# Sheet1.net
KiCad netlist of a schematic drawn in Altium Designer
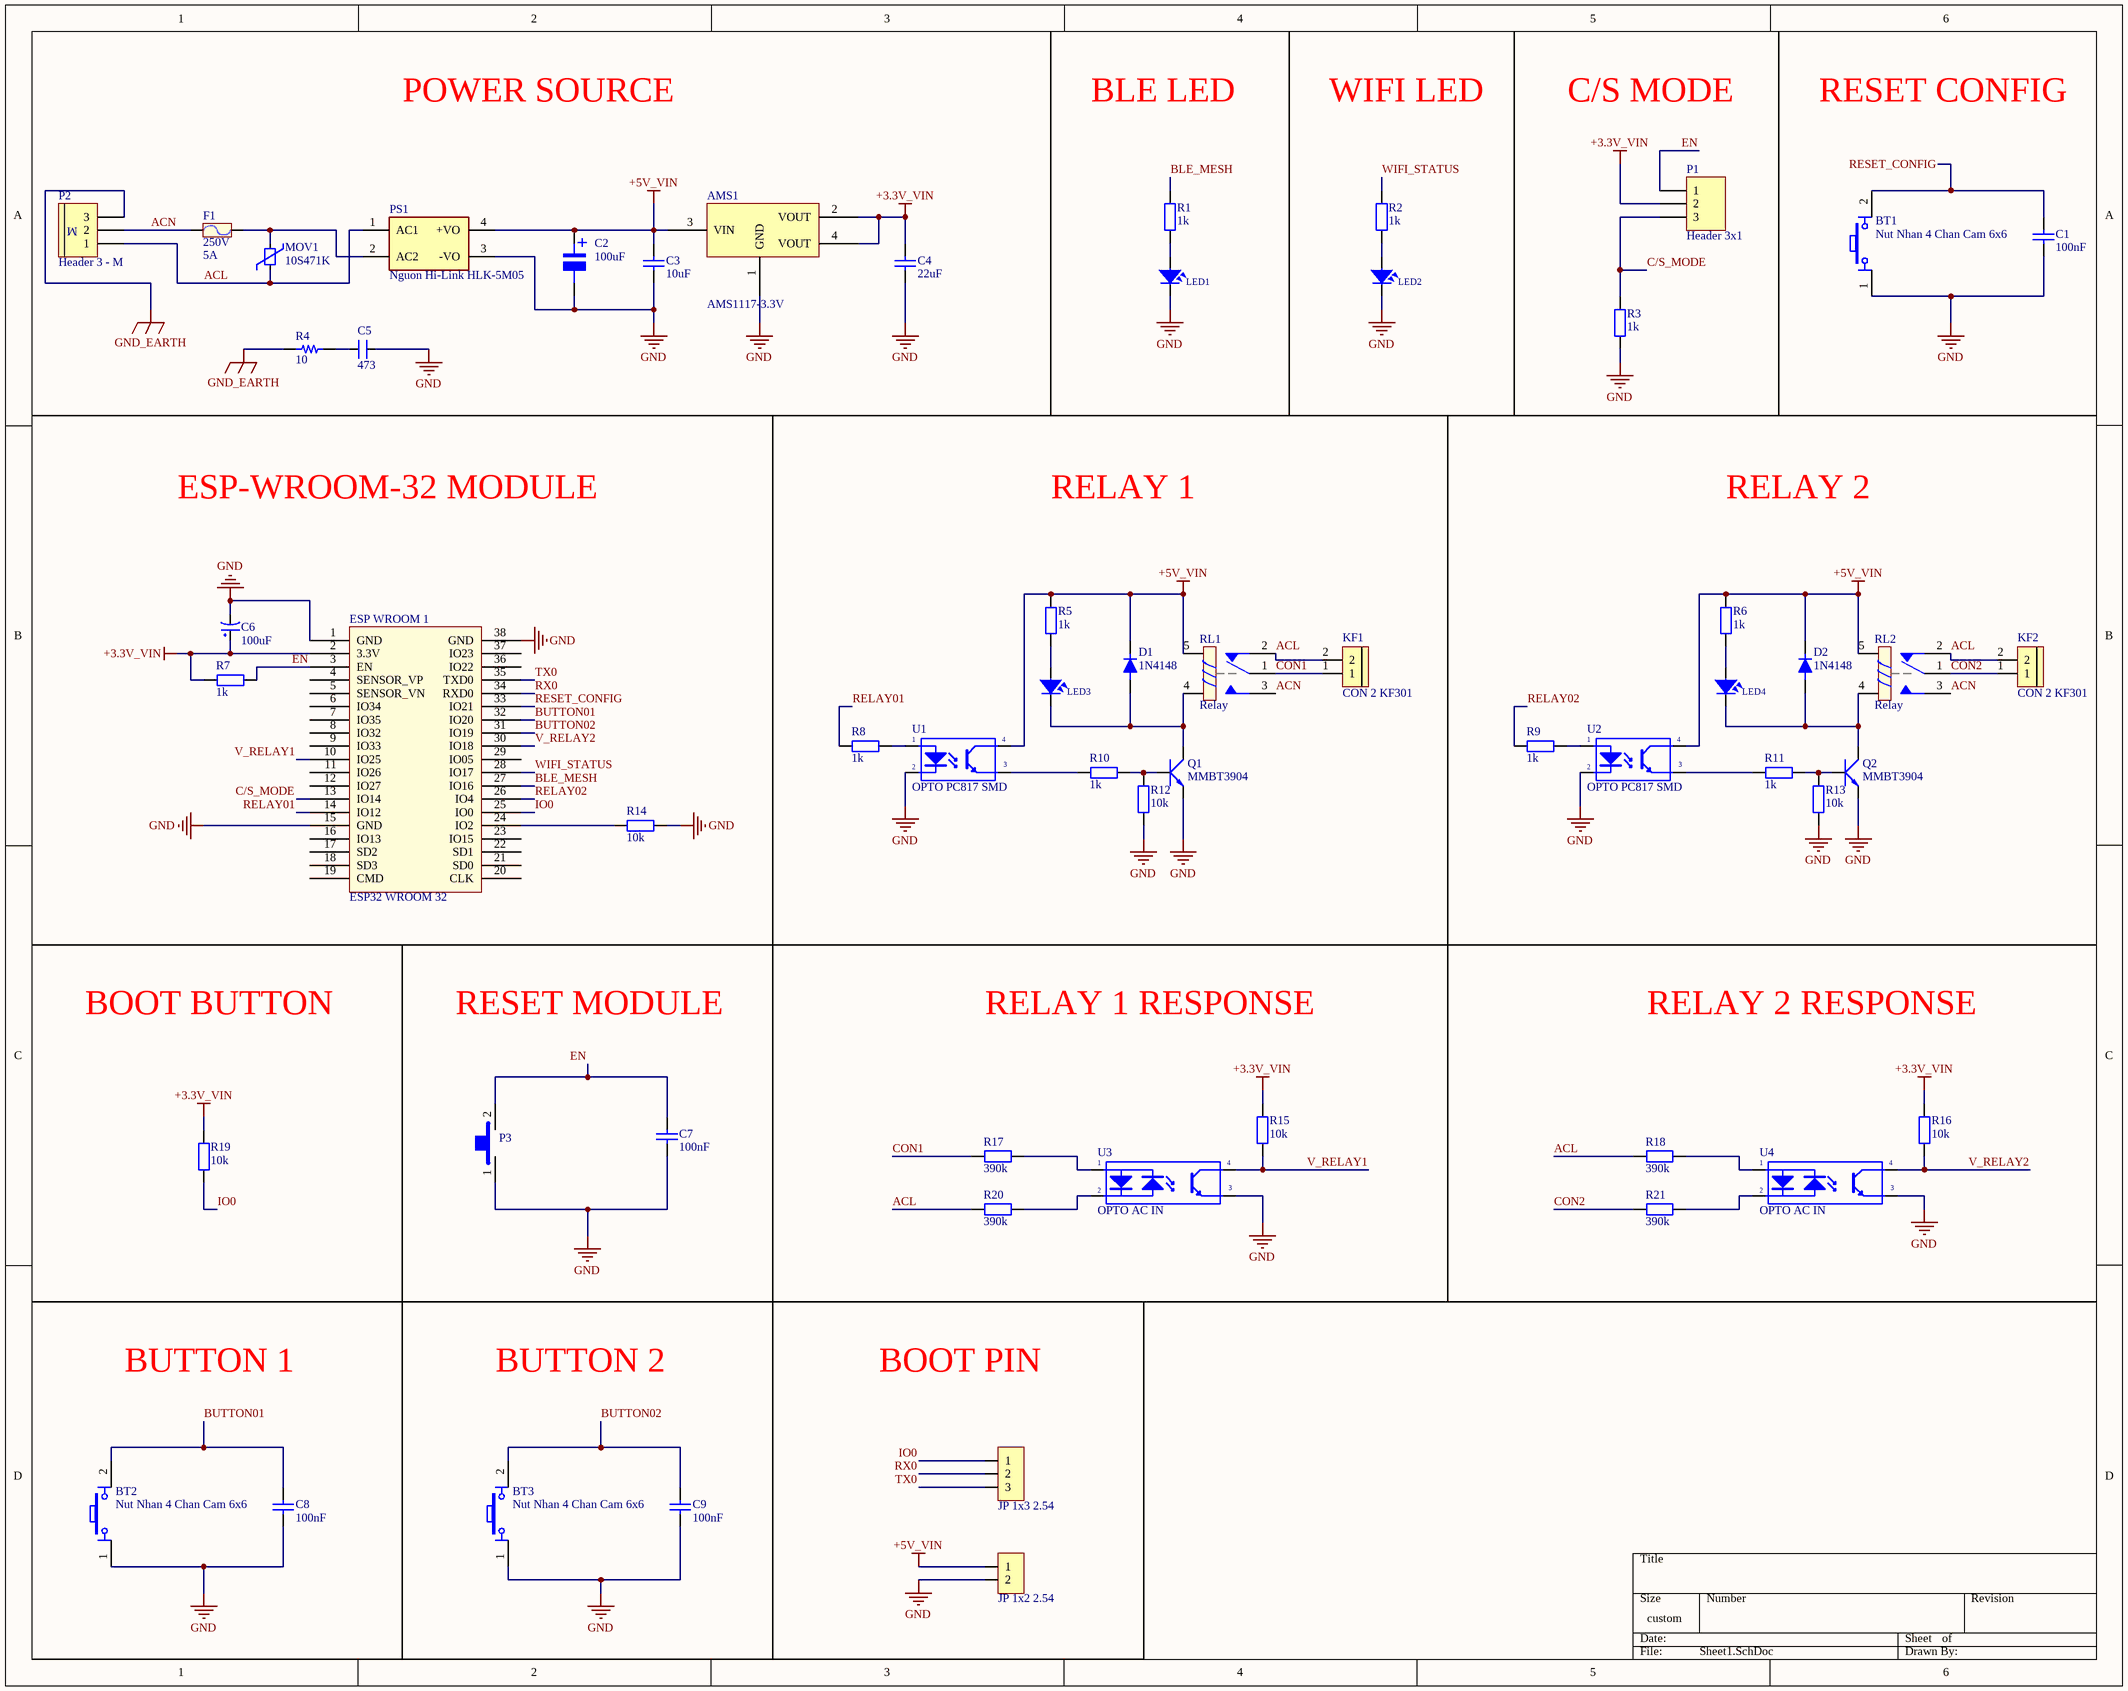
[diagram p0: Sheet1.SchDoc]

(export (version "E")
  (design (tool "Eeschema 10.0.6"))
  (components
    (comp (ref "AMS1")
      (value "AMS1117-3.3V")
      (footprint "SOT223")
      (description "Dán")
      (libsource (lib "Altium_Lib_by_KhueNguyenCreator") (part "AMS1117 SMD"))
    )
    (comp (ref "BT1")
      (value "Nut Nhan 4 Chan Cam 6x6")
      (footprint "Nut Nhan 4 Chan Cam 6x6")
      (description "Nut Nhan 4 Chan 6x6mm")
      (libsource (lib "Altium_Lib_by_KhueNguyenCreator") (part "Nut Nhan 4 Chan Cam 6x6"))
    )
    (comp (ref "BT2")
      (value "Nut Nhan 4 Chan Cam 6x6")
      (footprint "Nut Nhan 4 Chan Cam 6x6")
      (description "Nut Nhan 4 Chan 6x6mm")
      (libsource (lib "Altium_Lib_by_KhueNguyenCreator") (part "Nut Nhan 4 Chan Cam 6x6"))
    )
    (comp (ref "BT3")
      (value "Nut Nhan 4 Chan Cam 6x6")
      (footprint "Nut Nhan 4 Chan Cam 6x6")
      (description "Nut Nhan 4 Chan 6x6mm")
      (libsource (lib "Altium_Lib_by_KhueNguyenCreator") (part "Nut Nhan 4 Chan Cam 6x6"))
    )
    (comp (ref "C1")
      (value "100nF")
      (footprint "C0603C/1608MM")
      (description "Cap Ceramic 0.1uF 16V X7R 5% SMD 0603 125C T/R")
      (fields
        (field (name "MANUFACTURER") "Yageo")
        (field (name "MANUFACTURER PART NUMBER") "CC0603JRX7R7BB104")
      )
      (libsource (lib "Howard") (part "CAP CER 100nF 16V 5% X7R 0603"))
    )
    (comp (ref "C2")
      (value "100uF")
      (footprint "tu nhom 6.3 (d)")
      (description "Dán")
      (libsource (lib "Altium_Lib_by_KhueNguyenCreator") (part "Tu Nhom 100uF 16V"))
    )
    (comp (ref "C3")
      (value "10uF")
      (footprint "C0603C/1608MM")
      (description "CAP CER 0603 10uF 16V X7R 10%")
      (libsource (lib "Howard") (part "CAP CER 10uF 16V X7R 0603"))
    )
    (comp (ref "C4")
      (value "22uF")
      (footprint "C0603C/1608MM")
      (description "CAP CER 0603 10uF 16V X7R 10%")
      (libsource (lib "Howard") (part "CAP CER 10uF 16V X7R 0603"))
    )
    (comp (ref "C5")
      (value "473")
      (footprint "CN3")
      (description "Cap np W0.3")
      (fields (field (name "COPYRIGHT") "VanDungEvn"))
      (libsource (lib "syhaunguyen") (part "CN3"))
    )
    (comp (ref "C6")
      (value "100uF")
      (footprint "tu tantalum smd3528")
      (description "Dán")
      (libsource (lib "Altium_Lib_by_KhueNguyenCreator") (part "Tu tantalum 100uF 6.3V SMD3528"))
    )
    (comp (ref "C7")
      (value "100nF")
      (footprint "C0603C/1608MM")
      (description "Cap Ceramic 0.1uF 16V X7R 5% SMD 0603 125C T/R")
      (fields
        (field (name "MANUFACTURER") "Yageo")
        (field (name "MANUFACTURER PART NUMBER") "CC0603JRX7R7BB104")
      )
      (libsource (lib "Howard") (part "CAP CER 100nF 16V 5% X7R 0603"))
    )
    (comp (ref "C8")
      (value "100nF")
      (footprint "C0603C/1608MM")
      (description "Cap Ceramic 0.1uF 16V X7R 5% SMD 0603 125C T/R")
      (fields
        (field (name "MANUFACTURER") "Yageo")
        (field (name "MANUFACTURER PART NUMBER") "CC0603JRX7R7BB104")
      )
      (libsource (lib "Howard") (part "CAP CER 100nF 16V 5% X7R 0603"))
    )
    (comp (ref "C9")
      (value "100nF")
      (footprint "C0603C/1608MM")
      (description "Cap Ceramic 0.1uF 16V X7R 5% SMD 0603 125C T/R")
      (fields
        (field (name "MANUFACTURER") "Yageo")
        (field (name "MANUFACTURER PART NUMBER") "CC0603JRX7R7BB104")
      )
      (libsource (lib "Howard") (part "CAP CER 100nF 16V 5% X7R 0603"))
    )
    (comp (ref "D1")
      (value "1N4148")
      (footprint "SOD-323")
      (description "DIODE GEN PURP 75V 150MA DO35")
      (libsource (lib "Howard") (part "DIODE GEN PURP 75V 150MA DO35"))
    )
    (comp (ref "D2")
      (value "1N4148")
      (footprint "SOD-323")
      (description "DIODE GEN PURP 75V 150MA DO35")
      (libsource (lib "Howard") (part "DIODE GEN PURP 75V 150MA DO35"))
    )
    (comp (ref "ESP WROOM 1")
      (value "ESP32 WROOM 32")
      (footprint "ESP32-WROOM-32D")
      (libsource (lib "Altium_Lib_by_KhueNguyenCreator") (part "ESP32 WROOM 32"))
    )
    (comp (ref "F1")
      (value "5A220V")
      (footprint "FUSE_VERTICAL")
      (description "FUSE 220V 5A RADIAL")
      (fields (field (name "VOLTAGE - RATED") "250V") (field (name "CURRENT RATING (AMPS)") "5A"))
      (libsource (lib "Howard") (part "Fuse"))
    )
    (comp (ref "JP1")
      (value "JP 1x3 2.54")
      (footprint "JP 1x3 DT")
      (description "Cắm")
      (libsource (lib "Altium_Lib_by_KhueNguyenCreator") (part "JP 1x3 2.54 Duc Thang"))
    )
    (comp (ref "JP2")
      (value "JP 1x2 2.54")
      (footprint "JP 1x2 DT")
      (description "Cắm")
      (libsource (lib "Altium_Lib_by_KhueNguyenCreator") (part "JP 1x2 2.54 Duc Thang"))
    )
    (comp (ref "KF1")
      (value "CON 2 KF301")
      (footprint "Con 2 KF301 5.08")
      (description "Cắm")
      (libsource (lib "Altium_Lib_by_KhueNguyenCreator") (part "CON 2 KF301"))
    )
    (comp (ref "KF2")
      (value "CON 2 KF301")
      (footprint "Con 2 KF301 5.08")
      (description "Cắm")
      (libsource (lib "Altium_Lib_by_KhueNguyenCreator") (part "CON 2 KF301"))
    )
    (comp (ref "LED1")
      (value "LED SMD")
      (footprint "SM-LED-0805-Blue")
      (libsource (lib "My library altium") (part "LED SMD 0805"))
    )
    (comp (ref "LED2")
      (value "LED SMD")
      (footprint "SM-LED-0805-Blue")
      (libsource (lib "My library altium") (part "LED SMD 0805"))
    )
    (comp (ref "LED3")
      (value "LED SMD")
      (footprint "SM-LED-0805-Blue")
      (libsource (lib "My library altium") (part "LED SMD 0805"))
    )
    (comp (ref "LED4")
      (value "LED SMD")
      (footprint "SM-LED-0805-Blue")
      (libsource (lib "My library altium") (part "LED SMD 0805"))
    )
    (comp (ref "MOV1")
      (value "10S471K")
      (footprint "10S471K")
      (description "VARISTOR 470V 2.5KA DISC 10MM")
      (fields
        (field (name "MANUFACTURER2_PART#") "10D391K 390V 10mm")
        (field (name "MANUFACTURER1_PART#") "MOV-10D391K")
      )
      (libsource (lib "Howard") (part "MOV 10S471K"))
    )
    (comp (ref "P1")
      (value "Header 3x1")
      (footprint "HDR1X3")
      (description "Header, 3-Pin, pitch 2.54mm")
      (libsource (lib "BYTECH_HW_LIB_2019") (part "Header 3x1"))
    )
    (comp (ref "P2")
      (value "Header 3 - M")
      (footprint "Medium - Header 3")
      (description "Header, 3-Pin, Medium")
      (fields (field (name "PUBLISHER") "Altium Limited"))
      (libsource (lib "04.Header-Connecter") (part "Header 3 - M"))
    )
    (comp (ref "P3")
      (value "~")
      (footprint "SW 2P SMD")
      (description "SMD Mini Push Button Switch 2 Pin 3x6x2.7mm")
      (fields (field (name "MPN") "SMD Mini Push Button 2 SMD"))
      (libsource (lib "BYTECH_HW_LIB_2019") (part "Button 2 SMD"))
    )
    (comp (ref "PS1")
      (value "Nguon Hi-Link HLK-5M05")
      (footprint "Nguon HI-LINK 5M05")
      (description "AC DC 220V to 5V 5W 5Watt Isolated Switching Step-Down Power Supply Module Converter")
      (fields (field (name "MF") "Hi-link") (field (name "MP") "HLK-5M05"))
      (libsource (lib "Altium_Lib_by_KhueNguyenCreator") (part "Nguon Hi-Link HLK-5M05"))
    )
    (comp (ref "Q1")
      (value "MMBT3904")
      (footprint "Howard:SOT 23")
      (description "Bipolar (BJT) Transistor NPN 40 V 200 mA 300MHz 350 mW Surface Mount SOT-23")
      (fields (field (name "MANUFACTURER") "MCC") (field (name "MANUFACTURER PART NUMBER") "2SD882-GR-BP"))
      (libsource (lib "Howard") (part "TRANS NPN 40V 0.2A SOT23"))
    )
    (comp (ref "Q2")
      (value "MMBT3904")
      (footprint "Howard:SOT 23")
      (description "Bipolar (BJT) Transistor NPN 40 V 200 mA 300MHz 350 mW Surface Mount SOT-23")
      (fields (field (name "MANUFACTURER") "MCC") (field (name "MANUFACTURER PART NUMBER") "2SD882-GR-BP"))
      (libsource (lib "Howard") (part "TRANS NPN 40V 0.2A SOT23"))
    )
    (comp (ref "R1")
      (value "1k")
      (footprint "tro smd 0603")
      (description "Dán")
      (libsource (lib "Altium_Lib_by_KhueNguyenCreator") (part "Tro 0603 1% 1k"))
    )
    (comp (ref "R2")
      (value "1k")
      (footprint "tro smd 0603")
      (description "Dán")
      (libsource (lib "Altium_Lib_by_KhueNguyenCreator") (part "Tro 0603 1% 1k"))
    )
    (comp (ref "R3")
      (value "1k")
      (footprint "tro smd 0603")
      (description "Dán")
      (libsource (lib "Altium_Lib_by_KhueNguyenCreator") (part "Tro 0603 1% 1k"))
    )
    (comp (ref "R4")
      (value "10")
      (footprint "R1206B/3216MM")
      (description "Surface Mount Thick Film Resistor, RC Series, 3.3Mohm, 100 mW, - 5%, 50 V, 1206")
      (fields
        (field (name "MANUFACTURER") "Yageo")
        (field (name "MANUFACTURER PART NUMBER") "RC1206JR-073M3L")
      )
      (libsource (lib "Howard") (part "RES SMD 3.3M OHM 5% 1/4W 1206"))
    )
    (comp (ref "R5")
      (value "1k")
      (footprint "tro smd 0603")
      (description "Dán")
      (libsource (lib "Altium_Lib_by_KhueNguyenCreator") (part "Tro 0603 1% 1k"))
    )
    (comp (ref "R6")
      (value "1k")
      (footprint "tro smd 0603")
      (description "Dán")
      (libsource (lib "Altium_Lib_by_KhueNguyenCreator") (part "Tro 0603 1% 1k"))
    )
    (comp (ref "R7")
      (value "1k")
      (footprint "tro smd 0603")
      (description "Dán")
      (libsource (lib "Altium_Lib_by_KhueNguyenCreator") (part "Tro 0603 1% 1k"))
    )
    (comp (ref "R8")
      (value "1k")
      (footprint "tro smd 0603")
      (description "Dán")
      (libsource (lib "Altium_Lib_by_KhueNguyenCreator") (part "Tro 0603 1% 1k"))
    )
    (comp (ref "R9")
      (value "1k")
      (footprint "tro smd 0603")
      (description "Dán")
      (libsource (lib "Altium_Lib_by_KhueNguyenCreator") (part "Tro 0603 1% 1k"))
    )
    (comp (ref "R10")
      (value "1k")
      (footprint "tro smd 0603")
      (description "Dán")
      (libsource (lib "Altium_Lib_by_KhueNguyenCreator") (part "Tro 0603 1% 1k"))
    )
    (comp (ref "R11")
      (value "1k")
      (footprint "tro smd 0603")
      (description "Dán")
      (libsource (lib "Altium_Lib_by_KhueNguyenCreator") (part "Tro 0603 1% 1k"))
    )
    (comp (ref "R12")
      (value "10k")
      (footprint "tro smd 0603")
      (description "Dán")
      (libsource (lib "Altium_Lib_by_KhueNguyenCreator") (part "Tro 0603 1% 10k"))
    )
    (comp (ref "R13")
      (value "10k")
      (footprint "tro smd 0603")
      (description "Dán")
      (libsource (lib "Altium_Lib_by_KhueNguyenCreator") (part "Tro 0603 1% 10k"))
    )
    (comp (ref "R14")
      (value "10k")
      (footprint "tro smd 0603")
      (description "Dán")
      (libsource (lib "Altium_Lib_by_KhueNguyenCreator") (part "Tro 0603 1% 10k"))
    )
    (comp (ref "R15")
      (value "10k")
      (footprint "tro smd 0603")
      (description "Dán")
      (libsource (lib "Altium_Lib_by_KhueNguyenCreator") (part "Tro 0603 1% 10k"))
    )
    (comp (ref "R16")
      (value "10k")
      (footprint "tro smd 0603")
      (description "Dán")
      (libsource (lib "Altium_Lib_by_KhueNguyenCreator") (part "Tro 0603 1% 10k"))
    )
    (comp (ref "R17")
      (value "390k")
      (footprint "tro smd 1206")
      (description "Dán")
      (libsource (lib "Altium_Lib_by_KhueNguyenCreator") (part "Tro 1206 1% 390k"))
    )
    (comp (ref "R18")
      (value "390k")
      (footprint "tro smd 1206")
      (description "Dán")
      (libsource (lib "Altium_Lib_by_KhueNguyenCreator") (part "Tro 1206 1% 390k"))
    )
    (comp (ref "R19")
      (value "10k")
      (footprint "tro smd 0603")
      (description "Dán")
      (libsource (lib "Altium_Lib_by_KhueNguyenCreator") (part "Tro 0603 1% 10k"))
    )
    (comp (ref "R20")
      (value "390k")
      (footprint "tro smd 1206")
      (description "Dán")
      (libsource (lib "Altium_Lib_by_KhueNguyenCreator") (part "Tro 1206 1% 390k"))
    )
    (comp (ref "R21")
      (value "390k")
      (footprint "tro smd 1206")
      (description "Dán")
      (libsource (lib "Altium_Lib_by_KhueNguyenCreator") (part "Tro 1206 1% 390k"))
    )
    (comp (ref "RL1")
      (value "Relay")
      (footprint "Relay 5 Chan SRD")
      (description "Relay 5 Chan")
      (libsource (lib "Altium_Lib_by_KhueNguyenCreator") (part "Relay 5 Chan SRD"))
    )
    (comp (ref "RL2")
      (value "Relay")
      (footprint "Relay 5 Chan SRD")
      (description "Relay 5 Chan")
      (libsource (lib "Altium_Lib_by_KhueNguyenCreator") (part "Relay 5 Chan SRD"))
    )
    (comp (ref "U1")
      (value "OPTO PC817 SMD")
      (footprint "SOP4")
      (description "Single Opto")
      (libsource (lib "Altium_Lib_by_KhueNguyenCreator") (part "OPTO PC817 SMD"))
    )
    (comp (ref "U2")
      (value "OPTO PC817 SMD")
      (footprint "SOP4")
      (description "Single Opto")
      (libsource (lib "Altium_Lib_by_KhueNguyenCreator") (part "OPTO PC817 SMD"))
    )
    (comp (ref "U3")
      (value "OPTO AC IN")
      (footprint "LTV-354T")
      (description "AC INPUT Opto")
      (libsource (lib "Schlib1") (part "LTV-354T"))
    )
    (comp (ref "U4")
      (value "OPTO AC IN")
      (footprint "LTV-354T")
      (description "AC INPUT Opto")
      (libsource (lib "Schlib1") (part "LTV-354T"))
    )
  )
  (nets
    (net (code "1") (name "+3.3V_VIN") (class "Default")
      (node (ref "AMS1") (pin "2") (pinfunction "VOUT_2") (pintype "passive"))
      (node (ref "AMS1") (pin "4") (pinfunction "VOUT_4") (pintype "passive"))
      (node (ref "C4") (pin "2") (pinfunction "2_2") (pintype "passive"))
      (node (ref "C6") (pin "1") (pinfunction "1_1") (pintype "passive"))
      (node (ref "ESP WROOM 1") (pin "2") (pinfunction "3.3V_2") (pintype "passive"))
      (node (ref "P1") (pin "2") (pinfunction "2_2") (pintype "passive"))
      (node (ref "R15") (pin "2") (pinfunction "2_2") (pintype "passive"))
      (node (ref "R16") (pin "2") (pinfunction "2_2") (pintype "passive"))
      (node (ref "R19") (pin "1") (pinfunction "1_1") (pintype "passive"))
      (node (ref "R7") (pin "2") (pinfunction "2_2") (pintype "passive"))
    )
    (net (code "2") (name "+5V_VIN") (class "Default")
      (node (ref "AMS1") (pin "3") (pinfunction "VIN_3") (pintype "passive"))
      (node (ref "C2") (pin "1") (pinfunction "1_1") (pintype "passive"))
      (node (ref "C3") (pin "2") (pinfunction "2_2") (pintype "passive"))
      (node (ref "D1") (pin "2") (pinfunction "CATHODE_2") (pintype "passive"))
      (node (ref "D2") (pin "2") (pinfunction "CATHODE_2") (pintype "passive"))
      (node (ref "JP2") (pin "1") (pinfunction "1_1") (pintype "passive"))
      (node (ref "PS1") (pin "4") (pinfunction "+VO_4") (pintype "passive"))
      (node (ref "R5") (pin "2") (pinfunction "2_2") (pintype "passive"))
      (node (ref "R6") (pin "2") (pinfunction "2_2") (pintype "passive"))
      (node (ref "RL1") (pin "5") (pinfunction "5_5") (pintype "passive"))
      (node (ref "RL2") (pin "5") (pinfunction "5_5") (pintype "passive"))
      (node (ref "U1") (pin "4") (pinfunction "C_4") (pintype "passive"))
      (node (ref "U2") (pin "4") (pinfunction "C_4") (pintype "passive"))
    )
    (net (code "3") (name "/ACL") (class "Default")
      (node (ref "KF1") (pin "2") (pinfunction "2_2") (pintype "passive"))
      (node (ref "KF2") (pin "2") (pinfunction "2_2") (pintype "passive"))
      (node (ref "MOV1") (pin "2") (pinfunction "2_2") (pintype "passive"))
      (node (ref "P2") (pin "1") (pinfunction "1_1") (pintype "passive"))
      (node (ref "PS1") (pin "1") (pinfunction "AC1_1") (pintype "passive"))
      (node (ref "R18") (pin "1") (pinfunction "1_1") (pintype "passive"))
      (node (ref "R20") (pin "1") (pinfunction "1_1") (pintype "passive"))
      (node (ref "RL1") (pin "2") (pinfunction "2_2") (pintype "passive"))
      (node (ref "RL2") (pin "2") (pinfunction "2_2") (pintype "passive"))
    )
    (net (code "4") (name "/ACN") (class "Default")
      (node (ref "F1") (pin "2") (pinfunction "2_2") (pintype "passive"))
      (node (ref "P2") (pin "2") (pinfunction "2_2") (pintype "passive"))
      (node (ref "RL1") (pin "3") (pinfunction "3_3") (pintype "passive"))
      (node (ref "RL2") (pin "3") (pinfunction "3_3") (pintype "passive"))
    )
    (net (code "5") (name "/BLE_MESH") (class "Default")
      (node (ref "ESP WROOM 1") (pin "27") (pinfunction "IO16_27") (pintype "passive"))
      (node (ref "R1") (pin "2") (pinfunction "2_2") (pintype "passive"))
    )
    (net (code "6") (name "/BUTTON01") (class "Default")
      (node (ref "BT2") (pin "2") (pintype "passive"))
      (node (ref "C8") (pin "1") (pinfunction "1_1") (pintype "passive"))
      (node (ref "ESP WROOM 1") (pin "32") (pinfunction "IO20_32") (pintype "passive"))
    )
    (net (code "7") (name "/BUTTON02") (class "Default")
      (node (ref "BT3") (pin "2") (pintype "passive"))
      (node (ref "C9") (pin "1") (pinfunction "1_1") (pintype "passive"))
      (node (ref "ESP WROOM 1") (pin "31") (pinfunction "IO19_31") (pintype "passive"))
    )
    (net (code "8") (name "/CON1") (class "Default")
      (node (ref "KF1") (pin "1") (pinfunction "1_1") (pintype "passive"))
      (node (ref "R17") (pin "1") (pinfunction "1_1") (pintype "passive"))
      (node (ref "RL1") (pin "1") (pinfunction "1_1") (pintype "passive"))
    )
    (net (code "9") (name "/CON2") (class "Default")
      (node (ref "KF2") (pin "1") (pinfunction "1_1") (pintype "passive"))
      (node (ref "R21") (pin "1") (pinfunction "1_1") (pintype "passive"))
      (node (ref "RL2") (pin "1") (pinfunction "1_1") (pintype "passive"))
    )
    (net (code "10") (name "/C{slash}S_MODE") (class "Default")
      (node (ref "ESP WROOM 1") (pin "13") (pinfunction "IO14_13") (pintype "passive"))
      (node (ref "P1") (pin "3") (pinfunction "3_3") (pintype "passive"))
      (node (ref "R3") (pin "2") (pinfunction "2_2") (pintype "passive"))
    )
    (net (code "11") (name "/EN") (class "Default")
      (node (ref "C7") (pin "1") (pinfunction "1_1") (pintype "passive"))
      (node (ref "ESP WROOM 1") (pin "3") (pinfunction "EN_3") (pintype "passive"))
      (node (ref "P1") (pin "1") (pinfunction "1_1") (pintype "passive"))
      (node (ref "P3") (pin "2") (pinfunction "2_2") (pintype "passive"))
      (node (ref "R7") (pin "1") (pinfunction "1_1") (pintype "passive"))
    )
    (net (code "12") (name "/IO0") (class "Default")
      (node (ref "ESP WROOM 1") (pin "25") (pinfunction "IO0_25") (pintype "passive"))
      (node (ref "JP1") (pin "1") (pinfunction "1_1") (pintype "passive"))
      (node (ref "R19") (pin "2") (pinfunction "2_2") (pintype "passive"))
    )
    (net (code "13") (name "/RELAY01") (class "Default")
      (node (ref "ESP WROOM 1") (pin "14") (pinfunction "IO12_14") (pintype "passive"))
      (node (ref "R8") (pin "1") (pinfunction "1_1") (pintype "passive"))
    )
    (net (code "14") (name "/RELAY02") (class "Default")
      (node (ref "ESP WROOM 1") (pin "26") (pinfunction "IO4_26") (pintype "passive"))
      (node (ref "R9") (pin "1") (pinfunction "1_1") (pintype "passive"))
    )
    (net (code "15") (name "/RESET_CONFIG") (class "Default")
      (node (ref "BT1") (pin "2") (pintype "passive"))
      (node (ref "C1") (pin "1") (pinfunction "1_1") (pintype "passive"))
      (node (ref "ESP WROOM 1") (pin "33") (pinfunction "IO21_33") (pintype "passive"))
    )
    (net (code "16") (name "/RX0") (class "Default")
      (node (ref "ESP WROOM 1") (pin "34") (pinfunction "RXD0_34") (pintype "passive"))
      (node (ref "JP1") (pin "2") (pinfunction "2_2") (pintype "passive"))
    )
    (net (code "17") (name "/TX0") (class "Default")
      (node (ref "ESP WROOM 1") (pin "35") (pinfunction "TXD0_35") (pintype "passive"))
      (node (ref "JP1") (pin "3") (pinfunction "3_3") (pintype "passive"))
    )
    (net (code "18") (name "/V_RELAY1") (class "Default")
      (node (ref "ESP WROOM 1") (pin "10") (pinfunction "IO25_10") (pintype "passive"))
      (node (ref "R15") (pin "1") (pinfunction "1_1") (pintype "passive"))
      (node (ref "U3") (pin "4") (pinfunction "C_4") (pintype "passive"))
    )
    (net (code "19") (name "/V_RELAY2") (class "Default")
      (node (ref "ESP WROOM 1") (pin "30") (pinfunction "IO18_30") (pintype "passive"))
      (node (ref "R16") (pin "1") (pinfunction "1_1") (pintype "passive"))
      (node (ref "U4") (pin "4") (pinfunction "C_4") (pintype "passive"))
    )
    (net (code "20") (name "/WIFI_STATUS") (class "Default")
      (node (ref "ESP WROOM 1") (pin "28") (pinfunction "IO17_28") (pintype "passive"))
      (node (ref "R2") (pin "2") (pinfunction "2_2") (pintype "passive"))
    )
    (net (code "21") (name "GND") (class "Default")
      (node (ref "AMS1") (pin "1") (pinfunction "GND_1") (pintype "passive"))
      (node (ref "BT1") (pin "1") (pintype "passive"))
      (node (ref "BT2") (pin "1") (pintype "passive"))
      (node (ref "BT3") (pin "1") (pintype "passive"))
      (node (ref "C1") (pin "2") (pinfunction "2_2") (pintype "passive"))
      (node (ref "C2") (pin "2") (pinfunction "2_2") (pintype "passive"))
      (node (ref "C3") (pin "1") (pinfunction "1_1") (pintype "passive"))
      (node (ref "C4") (pin "1") (pinfunction "1_1") (pintype "passive"))
      (node (ref "C5") (pin "2") (pinfunction "2_2") (pintype "passive"))
      (node (ref "C6") (pin "2") (pinfunction "2_2") (pintype "passive"))
      (node (ref "C7") (pin "2") (pinfunction "2_2") (pintype "passive"))
      (node (ref "C8") (pin "2") (pinfunction "2_2") (pintype "passive"))
      (node (ref "C9") (pin "2") (pinfunction "2_2") (pintype "passive"))
      (node (ref "ESP WROOM 1") (pin "1") (pinfunction "GND_1") (pintype "passive"))
      (node (ref "ESP WROOM 1") (pin "15") (pinfunction "GND_15") (pintype "passive"))
      (node (ref "ESP WROOM 1") (pin "38") (pinfunction "GND_38") (pintype "passive"))
      (node (ref "JP2") (pin "2") (pinfunction "2_2") (pintype "passive"))
      (node (ref "LED1") (pin "2") (pinfunction "2_2") (pintype "passive"))
      (node (ref "LED2") (pin "2") (pinfunction "2_2") (pintype "passive"))
      (node (ref "P3") (pin "1") (pinfunction "1_1") (pintype "passive"))
      (node (ref "PS1") (pin "3") (pinfunction "-VO_3") (pintype "passive"))
      (node (ref "Q1") (pin "2") (pinfunction "E_2") (pintype "passive"))
      (node (ref "Q2") (pin "2") (pinfunction "E_2") (pintype "passive"))
      (node (ref "R12") (pin "1") (pinfunction "1_1") (pintype "passive"))
      (node (ref "R13") (pin "1") (pinfunction "1_1") (pintype "passive"))
      (node (ref "R14") (pin "1") (pinfunction "1_1") (pintype "passive"))
      (node (ref "R3") (pin "1") (pinfunction "1_1") (pintype "passive"))
      (node (ref "U1") (pin "2") (pinfunction "K_2") (pintype "passive"))
      (node (ref "U2") (pin "2") (pinfunction "K_2") (pintype "passive"))
      (node (ref "U3") (pin "3") (pinfunction "E_3") (pintype "passive"))
      (node (ref "U4") (pin "3") (pinfunction "E_3") (pintype "passive"))
    )
    (net (code "22") (name "GND_EARTH") (class "Default")
      (node (ref "P2") (pin "3") (pinfunction "3_3") (pintype "passive"))
      (node (ref "R4") (pin "1") (pinfunction "1_1") (pintype "passive"))
    )
    (net (code "23") (name "Net-(C5-Pad1)") (class "Default")
      (node (ref "C5") (pin "1") (pinfunction "1_1") (pintype "passive"))
      (node (ref "R4") (pin "2") (pinfunction "2_2") (pintype "passive"))
    )
    (net (code "24") (name "Net-(D1-ANODE)") (class "Default")
      (node (ref "D1") (pin "1") (pinfunction "ANODE_1") (pintype "passive"))
      (node (ref "LED3") (pin "2") (pinfunction "2_2") (pintype "passive"))
      (node (ref "Q1") (pin "3") (pinfunction "C_3") (pintype "passive"))
      (node (ref "RL1") (pin "4") (pinfunction "4_4") (pintype "passive"))
    )
    (net (code "25") (name "Net-(D2-ANODE)") (class "Default")
      (node (ref "D2") (pin "1") (pinfunction "ANODE_1") (pintype "passive"))
      (node (ref "LED4") (pin "2") (pinfunction "2_2") (pintype "passive"))
      (node (ref "Q2") (pin "3") (pinfunction "C_3") (pintype "passive"))
      (node (ref "RL2") (pin "4") (pinfunction "4_4") (pintype "passive"))
    )
    (net (code "26") (name "Net-(ESP WROOM 1-IO2)") (class "Default")
      (node (ref "ESP WROOM 1") (pin "24") (pinfunction "IO2_24") (pintype "passive"))
      (node (ref "R14") (pin "2") (pinfunction "2_2") (pintype "passive"))
    )
    (net (code "27") (name "Net-(LED1-Pad1)") (class "Default")
      (node (ref "LED1") (pin "1") (pinfunction "1_1") (pintype "passive"))
      (node (ref "R1") (pin "1") (pinfunction "1_1") (pintype "passive"))
    )
    (net (code "28") (name "Net-(LED2-Pad1)") (class "Default")
      (node (ref "LED2") (pin "1") (pinfunction "1_1") (pintype "passive"))
      (node (ref "R2") (pin "1") (pinfunction "1_1") (pintype "passive"))
    )
    (net (code "29") (name "Net-(LED3-Pad1)") (class "Default")
      (node (ref "LED3") (pin "1") (pinfunction "1_1") (pintype "passive"))
      (node (ref "R5") (pin "1") (pinfunction "1_1") (pintype "passive"))
    )
    (net (code "30") (name "Net-(LED4-Pad1)") (class "Default")
      (node (ref "LED4") (pin "1") (pinfunction "1_1") (pintype "passive"))
      (node (ref "R6") (pin "1") (pinfunction "1_1") (pintype "passive"))
    )
    (net (code "31") (name "Net-(PS1-AC2)") (class "Default")
      (node (ref "F1") (pin "1") (pinfunction "1_1") (pintype "passive"))
      (node (ref "MOV1") (pin "1") (pintype "passive"))
      (node (ref "PS1") (pin "2") (pinfunction "AC2_2") (pintype "passive"))
    )
    (net (code "32") (name "Net-(Q1-B)") (class "Default")
      (node (ref "Q1") (pin "1") (pinfunction "B_1") (pintype "passive"))
      (node (ref "R10") (pin "2") (pinfunction "2_2") (pintype "passive"))
      (node (ref "R12") (pin "2") (pinfunction "2_2") (pintype "passive"))
    )
    (net (code "33") (name "Net-(Q2-B)") (class "Default")
      (node (ref "Q2") (pin "1") (pinfunction "B_1") (pintype "passive"))
      (node (ref "R11") (pin "2") (pinfunction "2_2") (pintype "passive"))
      (node (ref "R13") (pin "2") (pinfunction "2_2") (pintype "passive"))
    )
    (net (code "34") (name "Net-(U1-A)") (class "Default")
      (node (ref "R8") (pin "2") (pinfunction "2_2") (pintype "passive"))
      (node (ref "U1") (pin "1") (pinfunction "A_1") (pintype "passive"))
    )
    (net (code "35") (name "Net-(U1-E)") (class "Default")
      (node (ref "R10") (pin "1") (pinfunction "1_1") (pintype "passive"))
      (node (ref "U1") (pin "3") (pinfunction "E_3") (pintype "passive"))
    )
    (net (code "36") (name "Net-(U2-A)") (class "Default")
      (node (ref "R9") (pin "2") (pinfunction "2_2") (pintype "passive"))
      (node (ref "U2") (pin "1") (pinfunction "A_1") (pintype "passive"))
    )
    (net (code "37") (name "Net-(U2-E)") (class "Default")
      (node (ref "R11") (pin "1") (pinfunction "1_1") (pintype "passive"))
      (node (ref "U2") (pin "3") (pinfunction "E_3") (pintype "passive"))
    )
    (net (code "38") (name "Net-(U3-A)") (class "Default")
      (node (ref "R17") (pin "2") (pinfunction "2_2") (pintype "passive"))
      (node (ref "U3") (pin "1") (pinfunction "A_1") (pintype "passive"))
    )
    (net (code "39") (name "Net-(U3-K)") (class "Default")
      (node (ref "R20") (pin "2") (pinfunction "2_2") (pintype "passive"))
      (node (ref "U3") (pin "2") (pinfunction "K_2") (pintype "passive"))
    )
    (net (code "40") (name "Net-(U4-A)") (class "Default")
      (node (ref "R18") (pin "2") (pinfunction "2_2") (pintype "passive"))
      (node (ref "U4") (pin "1") (pinfunction "A_1") (pintype "passive"))
    )
    (net (code "41") (name "Net-(U4-K)") (class "Default")
      (node (ref "R21") (pin "2") (pinfunction "2_2") (pintype "passive"))
      (node (ref "U4") (pin "2") (pinfunction "K_2") (pintype "passive"))
    )
    (net (code "42") (name "unconnected-(ESP WROOM 1-CLK-Pad20)") (class "Default")
      (node (ref "ESP WROOM 1") (pin "20") (pinfunction "CLK_20") (pintype "passive"))
    )
    (net (code "43") (name "unconnected-(ESP WROOM 1-CMD-Pad19)") (class "Default")
      (node (ref "ESP WROOM 1") (pin "19") (pinfunction "CMD_19") (pintype "passive"))
    )
    (net (code "44") (name "unconnected-(ESP WROOM 1-IO05-Pad29)") (class "Default")
      (node (ref "ESP WROOM 1") (pin "29") (pinfunction "IO05_29") (pintype "passive"))
    )
    (net (code "45") (name "unconnected-(ESP WROOM 1-IO13-Pad16)") (class "Default")
      (node (ref "ESP WROOM 1") (pin "16") (pinfunction "IO13_16") (pintype "passive"))
    )
    (net (code "46") (name "unconnected-(ESP WROOM 1-IO15-Pad23)") (class "Default")
      (node (ref "ESP WROOM 1") (pin "23") (pinfunction "IO15_23") (pintype "passive"))
    )
    (net (code "47") (name "unconnected-(ESP WROOM 1-IO22-Pad36)") (class "Default")
      (node (ref "ESP WROOM 1") (pin "36") (pinfunction "IO22_36") (pintype "passive"))
    )
    (net (code "48") (name "unconnected-(ESP WROOM 1-IO23-Pad37)") (class "Default")
      (node (ref "ESP WROOM 1") (pin "37") (pinfunction "IO23_37") (pintype "passive"))
    )
    (net (code "49") (name "unconnected-(ESP WROOM 1-IO26-Pad11)") (class "Default")
      (node (ref "ESP WROOM 1") (pin "11") (pinfunction "IO26_11") (pintype "passive"))
    )
    (net (code "50") (name "unconnected-(ESP WROOM 1-IO27-Pad12)") (class "Default")
      (node (ref "ESP WROOM 1") (pin "12") (pinfunction "IO27_12") (pintype "passive"))
    )
    (net (code "51") (name "unconnected-(ESP WROOM 1-IO32-Pad8)") (class "Default")
      (node (ref "ESP WROOM 1") (pin "8") (pinfunction "IO32_8") (pintype "passive"))
    )
    (net (code "52") (name "unconnected-(ESP WROOM 1-IO33-Pad9)") (class "Default")
      (node (ref "ESP WROOM 1") (pin "9") (pinfunction "IO33_9") (pintype "passive"))
    )
    (net (code "53") (name "unconnected-(ESP WROOM 1-IO34-Pad6)") (class "Default")
      (node (ref "ESP WROOM 1") (pin "6") (pinfunction "IO34_6") (pintype "passive"))
    )
    (net (code "54") (name "unconnected-(ESP WROOM 1-IO35-Pad7)") (class "Default")
      (node (ref "ESP WROOM 1") (pin "7") (pinfunction "IO35_7") (pintype "passive"))
    )
    (net (code "55") (name "unconnected-(ESP WROOM 1-SD0-Pad21)") (class "Default")
      (node (ref "ESP WROOM 1") (pin "21") (pinfunction "SD0_21") (pintype "passive"))
    )
    (net (code "56") (name "unconnected-(ESP WROOM 1-SD1-Pad22)") (class "Default")
      (node (ref "ESP WROOM 1") (pin "22") (pinfunction "SD1_22") (pintype "passive"))
    )
    (net (code "57") (name "unconnected-(ESP WROOM 1-SD2-Pad17)") (class "Default")
      (node (ref "ESP WROOM 1") (pin "17") (pinfunction "SD2_17") (pintype "passive"))
    )
    (net (code "58") (name "unconnected-(ESP WROOM 1-SD3-Pad18)") (class "Default")
      (node (ref "ESP WROOM 1") (pin "18") (pinfunction "SD3_18") (pintype "passive"))
    )
    (net (code "59") (name "unconnected-(ESP WROOM 1-SENSOR_VN-Pad5)") (class "Default")
      (node (ref "ESP WROOM 1") (pin "5") (pinfunction "SENSOR_VN_5") (pintype "passive"))
    )
    (net (code "60") (name "unconnected-(ESP WROOM 1-SENSOR_VP-Pad4)") (class "Default")
      (node (ref "ESP WROOM 1") (pin "4") (pinfunction "SENSOR_VP_4") (pintype "passive"))
    )
  )
)
